# test.net
KiCad netlist of a schematic drawn in EAGLE
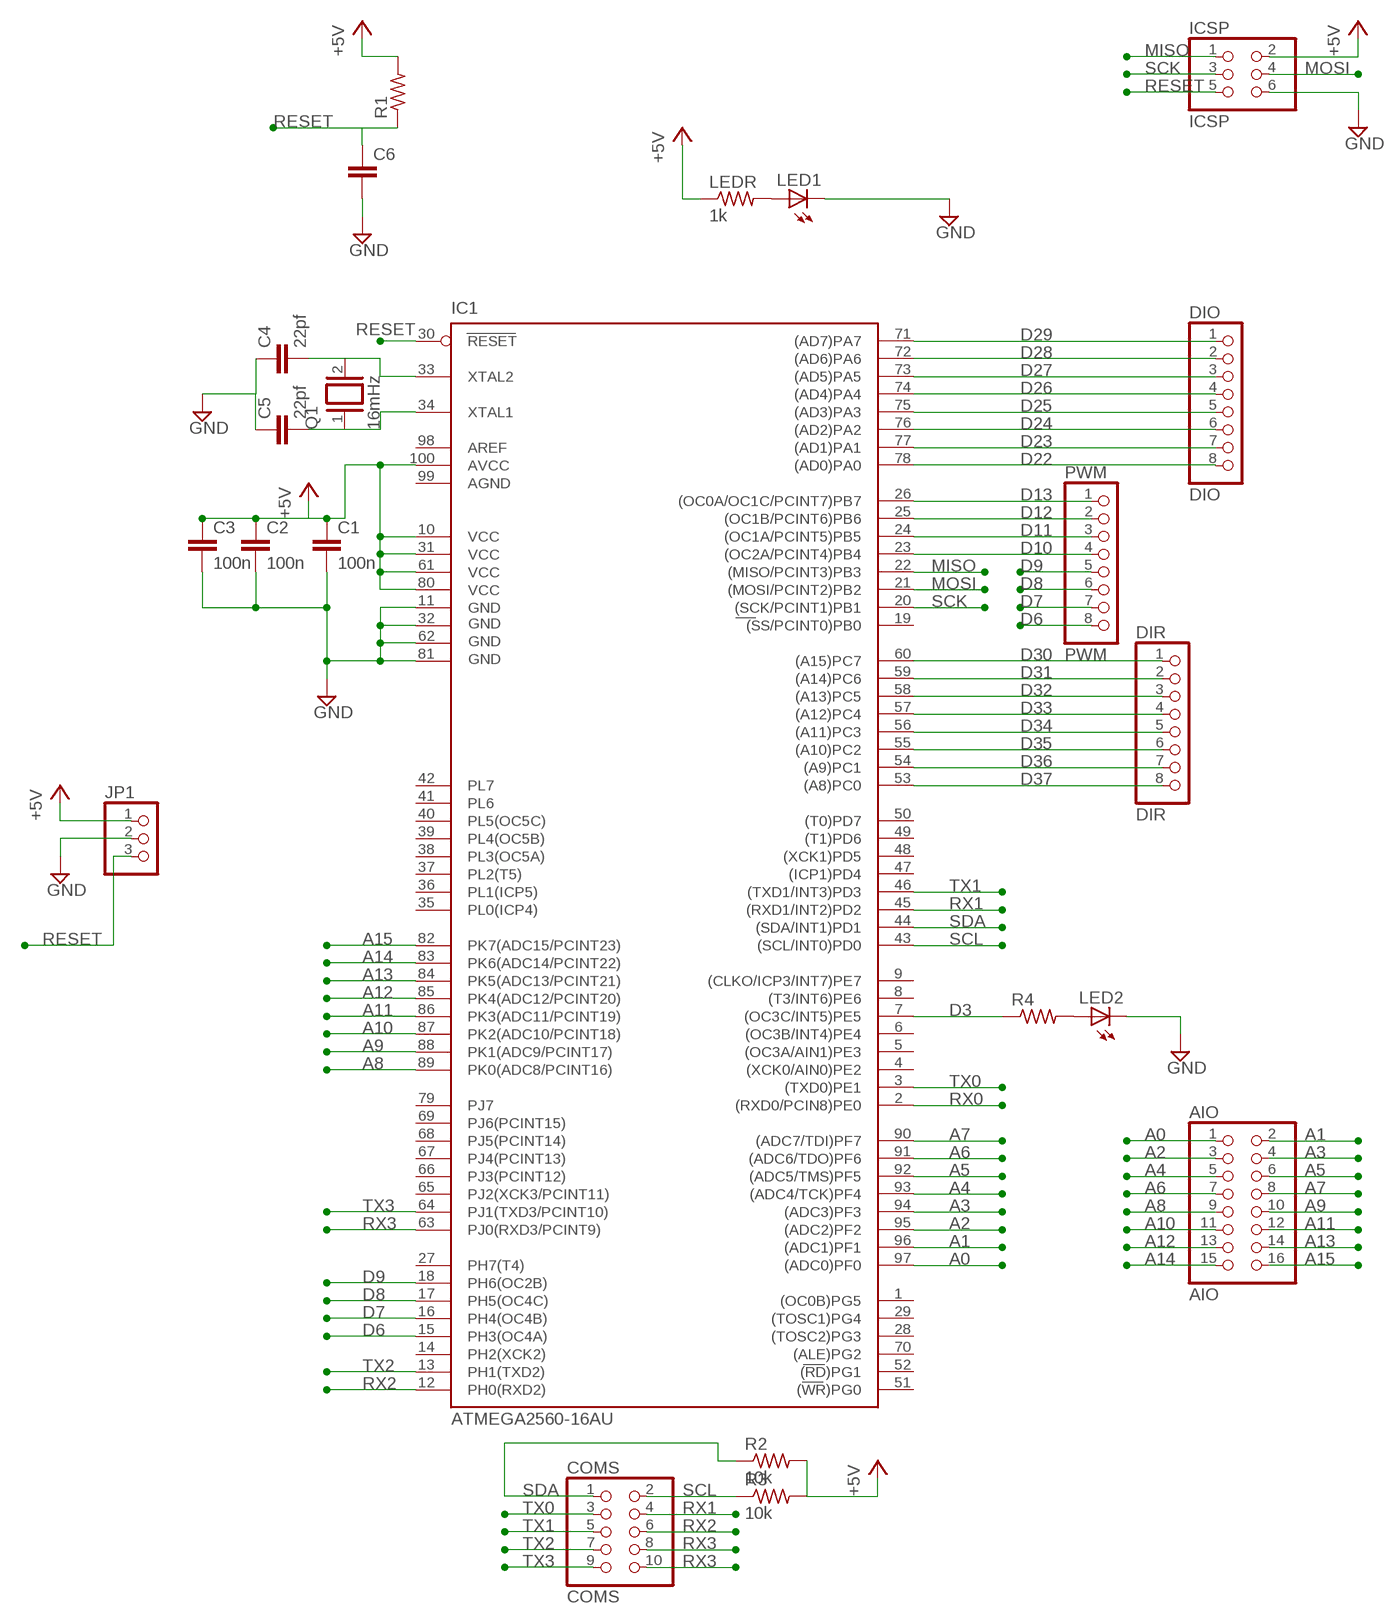
[diagram p0: schematic, sheet 1]

(export (version "E")
  (design (tool "Eeschema 10.0.6"))
  (components
    (comp (ref "AIO")
      (value "AIO")
      (footprint "eagle-import:2X08")
      (libsource (lib "eagle-import") (part "PINHD-2X8"))
    )
    (comp (ref "C1")
      (value "100n")
      (footprint "eagle-import:C5B3.5")
      (libsource (lib "eagle-import") (part "C5/3.5"))
    )
    (comp (ref "C2")
      (value "100n")
      (footprint "eagle-import:C5B3.5")
      (libsource (lib "eagle-import") (part "C5/3.5"))
    )
    (comp (ref "C3")
      (value "100n")
      (footprint "eagle-import:C5B3.5")
      (libsource (lib "eagle-import") (part "C5/3.5"))
    )
    (comp (ref "C4")
      (value "22pf")
      (footprint "eagle-import:C5B3.5")
      (libsource (lib "eagle-import") (part "C5/3.5"))
    )
    (comp (ref "C5")
      (value "22pf")
      (footprint "eagle-import:C5B3.5")
      (libsource (lib "eagle-import") (part "C5/3.5"))
    )
    (comp (ref "C6")
      (value "C5/3.5")
      (footprint "eagle-import:C5B3.5")
      (libsource (lib "eagle-import") (part "C5/3.5"))
    )
    (comp (ref "COMS")
      (value "COMS")
      (footprint "eagle-import:2X05")
      (libsource (lib "eagle-import") (part "PINHD-2X5"))
    )
    (comp (ref "DIO")
      (value "DIO")
      (footprint "eagle-import:1X08")
      (libsource (lib "eagle-import") (part "PINHD-1X8"))
    )
    (comp (ref "DIR")
      (value "DIR")
      (footprint "eagle-import:1X08")
      (libsource (lib "eagle-import") (part "PINHD-1X8"))
    )
    (comp (ref "IC1")
      (value "ATMEGA2560-16AU")
      (footprint "eagle-import:TQFP100")
      (libsource (lib "eagle-import") (part "ATMEGAAU2560-16"))
    )
    (comp (ref "ICSP")
      (value "ICSP")
      (footprint "eagle-import:2X03")
      (libsource (lib "eagle-import") (part "PINHD-2X3"))
    )
    (comp (ref "JP1")
      (value "PINHD-1X3")
      (footprint "eagle-import:1X03")
      (libsource (lib "eagle-import") (part "PINHD-1X3"))
    )
    (comp (ref "LED1")
      (value "LEDB156")
      (footprint "eagle-import:Q62902-B156")
      (libsource (lib "eagle-import") (part "LEDB156"))
    )
    (comp (ref "LED2")
      (value "LEDB156")
      (footprint "eagle-import:Q62902-B156")
      (libsource (lib "eagle-import") (part "LEDB156"))
    )
    (comp (ref "LEDR")
      (value "1k")
      (footprint "eagle-import:0207_7")
      (libsource (lib "eagle-import") (part "R-US_0207/7"))
    )
    (comp (ref "PWM")
      (value "PWM")
      (footprint "eagle-import:1X08")
      (libsource (lib "eagle-import") (part "PINHD-1X8"))
    )
    (comp (ref "Q1")
      (value "16mHz")
      (footprint "eagle-import:QS")
      (libsource (lib "eagle-import") (part "XTAL/S"))
    )
    (comp (ref "R1")
      (value "R-US_0207/7")
      (footprint "eagle-import:0207_7")
      (libsource (lib "eagle-import") (part "R-US_0207/7"))
    )
    (comp (ref "R2")
      (value "10k")
      (footprint "eagle-import:0207_7")
      (libsource (lib "eagle-import") (part "resistor_R-US_0207/7"))
    )
    (comp (ref "R3")
      (value "10k")
      (footprint "eagle-import:0207_7")
      (libsource (lib "eagle-import") (part "resistor_R-US_0207/7"))
    )
    (comp (ref "R4")
      (value "R-US_0207/7")
      (footprint "eagle-import:0207_7")
      (libsource (lib "eagle-import") (part "resistor_R-US_0207/7"))
    )
  )
  (nets
    (net (code "1") (name "+5V") (class "Default")
      (node (ref "C1") (pin "1") (pinfunction "1_1") (pintype "passive"))
      (node (ref "C2") (pin "1") (pinfunction "1_1") (pintype "passive"))
      (node (ref "C3") (pin "1") (pinfunction "1_1") (pintype "passive"))
      (node (ref "IC1") (pin "10") (pinfunction "VCC_10") (pintype "power_in"))
      (node (ref "IC1") (pin "100") (pinfunction "AVCC_100") (pintype "power_in"))
      (node (ref "IC1") (pin "31") (pinfunction "VCC1_31") (pintype "power_in"))
      (node (ref "IC1") (pin "61") (pinfunction "VCC2_61") (pintype "power_in"))
      (node (ref "IC1") (pin "80") (pinfunction "VCC3_80") (pintype "power_in"))
      (node (ref "ICSP") (pin "2") (pinfunction "2_2") (pintype "passive"))
      (node (ref "JP1") (pin "1") (pinfunction "1_1") (pintype "passive"))
      (node (ref "LEDR") (pin "1") (pinfunction "1_1") (pintype "passive"))
      (node (ref "R1") (pin "2") (pinfunction "2_2") (pintype "passive"))
      (node (ref "R2") (pin "2") (pinfunction "2_2") (pintype "passive"))
      (node (ref "R3") (pin "2") (pinfunction "2_2") (pintype "passive"))
    )
    (net (code "2") (name "/A0") (class "Default")
      (node (ref "AIO") (pin "1") (pinfunction "1_1") (pintype "passive"))
      (node (ref "IC1") (pin "97") (pinfunction "(ADC0)PF0_97") (pintype "bidirectional"))
    )
    (net (code "3") (name "/A1") (class "Default")
      (node (ref "AIO") (pin "2") (pinfunction "2_2") (pintype "passive"))
      (node (ref "IC1") (pin "96") (pinfunction "(ADC1)PF1_96") (pintype "bidirectional"))
    )
    (net (code "4") (name "/A2") (class "Default")
      (node (ref "AIO") (pin "3") (pinfunction "3_3") (pintype "passive"))
      (node (ref "IC1") (pin "95") (pinfunction "(ADC2)PF2_95") (pintype "bidirectional"))
    )
    (net (code "5") (name "/A3") (class "Default")
      (node (ref "AIO") (pin "4") (pinfunction "4_4") (pintype "passive"))
      (node (ref "IC1") (pin "94") (pinfunction "(ADC3)PF3_94") (pintype "bidirectional"))
    )
    (net (code "6") (name "/A4") (class "Default")
      (node (ref "AIO") (pin "5") (pinfunction "5_5") (pintype "passive"))
      (node (ref "IC1") (pin "93") (pinfunction "(ADC4/TCK)PF4_93") (pintype "bidirectional"))
    )
    (net (code "7") (name "/A5") (class "Default")
      (node (ref "AIO") (pin "6") (pinfunction "6_6") (pintype "passive"))
      (node (ref "IC1") (pin "92") (pinfunction "(ADC5/TMS)PF5_92") (pintype "bidirectional"))
    )
    (net (code "8") (name "/A6") (class "Default")
      (node (ref "AIO") (pin "7") (pinfunction "7_7") (pintype "passive"))
      (node (ref "IC1") (pin "91") (pinfunction "(ADC6/TDO)PF6_91") (pintype "bidirectional"))
    )
    (net (code "9") (name "/A7") (class "Default")
      (node (ref "AIO") (pin "8") (pinfunction "8_8") (pintype "passive"))
      (node (ref "IC1") (pin "90") (pinfunction "(ADC7/TDI)PF7_90") (pintype "bidirectional"))
    )
    (net (code "10") (name "/A8") (class "Default")
      (node (ref "AIO") (pin "9") (pinfunction "9_9") (pintype "passive"))
      (node (ref "IC1") (pin "89") (pinfunction "PK0(ADC8/PCINT16)_89") (pintype "bidirectional"))
    )
    (net (code "11") (name "/A9") (class "Default")
      (node (ref "AIO") (pin "10") (pinfunction "10_10") (pintype "passive"))
      (node (ref "IC1") (pin "88") (pinfunction "PK1(ADC9/PCINT17)_88") (pintype "bidirectional"))
    )
    (net (code "12") (name "/A10") (class "Default")
      (node (ref "AIO") (pin "11") (pinfunction "11_11") (pintype "passive"))
      (node (ref "IC1") (pin "87") (pinfunction "PK2(ADC10/PCINT18)_87") (pintype "bidirectional"))
    )
    (net (code "13") (name "/A11") (class "Default")
      (node (ref "AIO") (pin "12") (pinfunction "12_12") (pintype "passive"))
      (node (ref "IC1") (pin "86") (pinfunction "PK3(ADC11/PCINT19)_86") (pintype "bidirectional"))
    )
    (net (code "14") (name "/A12") (class "Default")
      (node (ref "AIO") (pin "13") (pinfunction "13_13") (pintype "passive"))
      (node (ref "IC1") (pin "85") (pinfunction "PK4(ADC12/PCINT20)_85") (pintype "bidirectional"))
    )
    (net (code "15") (name "/A13") (class "Default")
      (node (ref "AIO") (pin "14") (pinfunction "14_14") (pintype "passive"))
      (node (ref "IC1") (pin "84") (pinfunction "PK5(ADC13/PCINT21)_84") (pintype "bidirectional"))
    )
    (net (code "16") (name "/A14") (class "Default")
      (node (ref "AIO") (pin "15") (pinfunction "15_15") (pintype "passive"))
      (node (ref "IC1") (pin "83") (pinfunction "PK6(ADC14/PCINT22)_83") (pintype "bidirectional"))
    )
    (net (code "17") (name "/A15") (class "Default")
      (node (ref "AIO") (pin "16") (pinfunction "16_16") (pintype "passive"))
      (node (ref "IC1") (pin "82") (pinfunction "PK7(ADC15/PCINT23)_82") (pintype "bidirectional"))
    )
    (net (code "18") (name "/AGND") (class "Default")
      (node (ref "IC1") (pin "99") (pinfunction "AGND_99") (pintype "power_in"))
    )
    (net (code "19") (name "/D3") (class "Default")
      (node (ref "IC1") (pin "7") (pinfunction "(OC3C/INT5)PE5_7") (pintype "bidirectional"))
      (node (ref "R4") (pin "1") (pinfunction "1_1") (pintype "passive"))
    )
    (net (code "20") (name "/D6") (class "Default")
      (node (ref "IC1") (pin "15") (pinfunction "PH3(OC4A)_15") (pintype "bidirectional"))
      (node (ref "PWM") (pin "8") (pinfunction "8_8") (pintype "passive"))
    )
    (net (code "21") (name "/D7") (class "Default")
      (node (ref "IC1") (pin "16") (pinfunction "PH4(OC4B)_16") (pintype "bidirectional"))
      (node (ref "PWM") (pin "7") (pinfunction "7_7") (pintype "passive"))
    )
    (net (code "22") (name "/D8") (class "Default")
      (node (ref "IC1") (pin "17") (pinfunction "PH5(OC4C)_17") (pintype "bidirectional"))
      (node (ref "PWM") (pin "6") (pinfunction "6_6") (pintype "passive"))
    )
    (net (code "23") (name "/D9") (class "Default")
      (node (ref "IC1") (pin "18") (pinfunction "PH6(OC2B)_18") (pintype "bidirectional"))
      (node (ref "PWM") (pin "5") (pinfunction "5_5") (pintype "passive"))
    )
    (net (code "24") (name "/D10") (class "Default")
      (node (ref "IC1") (pin "23") (pinfunction "(OC2A/PCINT4)PB4_23") (pintype "bidirectional"))
      (node (ref "PWM") (pin "4") (pinfunction "4_4") (pintype "passive"))
    )
    (net (code "25") (name "/D11") (class "Default")
      (node (ref "IC1") (pin "24") (pinfunction "(OC1A/PCINT5)PB5_24") (pintype "bidirectional"))
      (node (ref "PWM") (pin "3") (pinfunction "3_3") (pintype "passive"))
    )
    (net (code "26") (name "/D12") (class "Default")
      (node (ref "IC1") (pin "25") (pinfunction "(OC1B/PCINT6)PB6_25") (pintype "bidirectional"))
      (node (ref "PWM") (pin "2") (pinfunction "2_2") (pintype "passive"))
    )
    (net (code "27") (name "/D13") (class "Default")
      (node (ref "IC1") (pin "26") (pinfunction "(OC0A/OC1C/PCINT7)PB7_26") (pintype "bidirectional"))
      (node (ref "PWM") (pin "1") (pinfunction "1_1") (pintype "passive"))
    )
    (net (code "28") (name "/D22") (class "Default")
      (node (ref "DIO") (pin "8") (pinfunction "8_8") (pintype "passive"))
      (node (ref "IC1") (pin "78") (pinfunction "(AD0)PA0_78") (pintype "bidirectional"))
    )
    (net (code "29") (name "/D23") (class "Default")
      (node (ref "DIO") (pin "7") (pinfunction "7_7") (pintype "passive"))
      (node (ref "IC1") (pin "77") (pinfunction "(AD1)PA1_77") (pintype "bidirectional"))
    )
    (net (code "30") (name "/D24") (class "Default")
      (node (ref "DIO") (pin "6") (pinfunction "6_6") (pintype "passive"))
      (node (ref "IC1") (pin "76") (pinfunction "(AD2)PA2_76") (pintype "bidirectional"))
    )
    (net (code "31") (name "/D25") (class "Default")
      (node (ref "DIO") (pin "5") (pinfunction "5_5") (pintype "passive"))
      (node (ref "IC1") (pin "75") (pinfunction "(AD3)PA3_75") (pintype "bidirectional"))
    )
    (net (code "32") (name "/D26") (class "Default")
      (node (ref "DIO") (pin "4") (pinfunction "4_4") (pintype "passive"))
      (node (ref "IC1") (pin "74") (pinfunction "(AD4)PA4_74") (pintype "bidirectional"))
    )
    (net (code "33") (name "/D27") (class "Default")
      (node (ref "DIO") (pin "3") (pinfunction "3_3") (pintype "passive"))
      (node (ref "IC1") (pin "73") (pinfunction "(AD5)PA5_73") (pintype "bidirectional"))
    )
    (net (code "34") (name "/D28") (class "Default")
      (node (ref "DIO") (pin "2") (pinfunction "2_2") (pintype "passive"))
      (node (ref "IC1") (pin "72") (pinfunction "(AD6)PA6_72") (pintype "bidirectional"))
    )
    (net (code "35") (name "/D29") (class "Default")
      (node (ref "DIO") (pin "1") (pinfunction "1_1") (pintype "passive"))
      (node (ref "IC1") (pin "71") (pinfunction "(AD7)PA7_71") (pintype "bidirectional"))
    )
    (net (code "36") (name "/D30") (class "Default")
      (node (ref "DIR") (pin "1") (pinfunction "1_1") (pintype "passive"))
      (node (ref "IC1") (pin "60") (pinfunction "(A15)PC7_60") (pintype "bidirectional"))
    )
    (net (code "37") (name "/D31") (class "Default")
      (node (ref "DIR") (pin "2") (pinfunction "2_2") (pintype "passive"))
      (node (ref "IC1") (pin "59") (pinfunction "(A14)PC6_59") (pintype "bidirectional"))
    )
    (net (code "38") (name "/D32") (class "Default")
      (node (ref "DIR") (pin "3") (pinfunction "3_3") (pintype "passive"))
      (node (ref "IC1") (pin "58") (pinfunction "(A13)PC5_58") (pintype "bidirectional"))
    )
    (net (code "39") (name "/D33") (class "Default")
      (node (ref "DIR") (pin "4") (pinfunction "4_4") (pintype "passive"))
      (node (ref "IC1") (pin "57") (pinfunction "(A12)PC4_57") (pintype "bidirectional"))
    )
    (net (code "40") (name "/D34") (class "Default")
      (node (ref "DIR") (pin "5") (pinfunction "5_5") (pintype "passive"))
      (node (ref "IC1") (pin "56") (pinfunction "(A11)PC3_56") (pintype "bidirectional"))
    )
    (net (code "41") (name "/D35") (class "Default")
      (node (ref "DIR") (pin "6") (pinfunction "6_6") (pintype "passive"))
      (node (ref "IC1") (pin "55") (pinfunction "(A10)PC2_55") (pintype "bidirectional"))
    )
    (net (code "42") (name "/D36") (class "Default")
      (node (ref "DIR") (pin "7") (pinfunction "7_7") (pintype "passive"))
      (node (ref "IC1") (pin "54") (pinfunction "(A9)PC1_54") (pintype "bidirectional"))
    )
    (net (code "43") (name "/D37") (class "Default")
      (node (ref "DIR") (pin "8") (pinfunction "8_8") (pintype "passive"))
      (node (ref "IC1") (pin "53") (pinfunction "(A8)PC0_53") (pintype "bidirectional"))
    )
    (net (code "44") (name "/MISO") (class "Default")
      (node (ref "IC1") (pin "22") (pinfunction "(MISO/PCINT3)PB3_22") (pintype "bidirectional"))
      (node (ref "ICSP") (pin "1") (pinfunction "1_1") (pintype "passive"))
    )
    (net (code "45") (name "/MOSI") (class "Default")
      (node (ref "IC1") (pin "21") (pinfunction "(MOSI/PCINT2)PB2_21") (pintype "bidirectional"))
      (node (ref "ICSP") (pin "4") (pinfunction "4_4") (pintype "passive"))
    )
    (net (code "46") (name "/RESET") (class "Default")
      (node (ref "C6") (pin "1") (pinfunction "1_1") (pintype "passive"))
      (node (ref "IC1") (pin "30") (pinfunction "RESET_30") (pintype "input"))
      (node (ref "ICSP") (pin "5") (pinfunction "5_5") (pintype "passive"))
      (node (ref "JP1") (pin "3") (pinfunction "3_3") (pintype "passive"))
      (node (ref "R1") (pin "1") (pinfunction "1_1") (pintype "passive"))
    )
    (net (code "47") (name "/RX0") (class "Default")
      (node (ref "IC1") (pin "2") (pinfunction "(RXD0/PCIN8)PE0_2") (pintype "bidirectional"))
    )
    (net (code "48") (name "/RX1") (class "Default")
      (node (ref "COMS") (pin "4") (pinfunction "4_4") (pintype "passive"))
      (node (ref "IC1") (pin "45") (pinfunction "(RXD1/INT2)PD2_45") (pintype "bidirectional"))
    )
    (net (code "49") (name "/RX2") (class "Default")
      (node (ref "COMS") (pin "6") (pinfunction "6_6") (pintype "passive"))
      (node (ref "IC1") (pin "12") (pinfunction "PH0(RXD2)_12") (pintype "bidirectional"))
    )
    (net (code "50") (name "/RX3") (class "Default")
      (node (ref "COMS") (pin "10") (pinfunction "10_10") (pintype "passive"))
      (node (ref "COMS") (pin "8") (pinfunction "8_8") (pintype "passive"))
      (node (ref "IC1") (pin "63") (pinfunction "PJ0(RXD3/PCINT9)_63") (pintype "bidirectional"))
    )
    (net (code "51") (name "/SCK") (class "Default")
      (node (ref "IC1") (pin "20") (pinfunction "(SCK/PCINT1)PB1_20") (pintype "bidirectional"))
      (node (ref "ICSP") (pin "3") (pinfunction "3_3") (pintype "passive"))
    )
    (net (code "52") (name "/SCL") (class "Default")
      (node (ref "COMS") (pin "2") (pinfunction "2_2") (pintype "passive"))
      (node (ref "IC1") (pin "43") (pinfunction "(SCL/INT0)PD0_43") (pintype "bidirectional"))
      (node (ref "R3") (pin "1") (pinfunction "1_1") (pintype "passive"))
    )
    (net (code "53") (name "/SDA") (class "Default")
      (node (ref "COMS") (pin "1") (pinfunction "1_1") (pintype "passive"))
      (node (ref "IC1") (pin "44") (pinfunction "(SDA/INT1)PD1_44") (pintype "bidirectional"))
      (node (ref "R2") (pin "1") (pinfunction "1_1") (pintype "passive"))
    )
    (net (code "54") (name "/TX0") (class "Default")
      (node (ref "COMS") (pin "3") (pinfunction "3_3") (pintype "passive"))
      (node (ref "IC1") (pin "3") (pinfunction "(TXD0)PE1_3") (pintype "bidirectional"))
    )
    (net (code "55") (name "/TX1") (class "Default")
      (node (ref "COMS") (pin "5") (pinfunction "5_5") (pintype "passive"))
      (node (ref "IC1") (pin "46") (pinfunction "(TXD1/INT3)PD3_46") (pintype "bidirectional"))
    )
    (net (code "56") (name "/TX2") (class "Default")
      (node (ref "COMS") (pin "7") (pinfunction "7_7") (pintype "passive"))
      (node (ref "IC1") (pin "13") (pinfunction "PH1(TXD2)_13") (pintype "bidirectional"))
    )
    (net (code "57") (name "/TX3") (class "Default")
      (node (ref "COMS") (pin "9") (pinfunction "9_9") (pintype "passive"))
      (node (ref "IC1") (pin "64") (pinfunction "PJ1(TXD3/PCINT10)_64") (pintype "bidirectional"))
    )
    (net (code "58") (name "GND") (class "Default")
      (node (ref "C1") (pin "2") (pinfunction "2_2") (pintype "passive"))
      (node (ref "C2") (pin "2") (pinfunction "2_2") (pintype "passive"))
      (node (ref "C3") (pin "2") (pinfunction "2_2") (pintype "passive"))
      (node (ref "C4") (pin "1") (pinfunction "1_1") (pintype "passive"))
      (node (ref "C5") (pin "1") (pinfunction "1_1") (pintype "passive"))
      (node (ref "C6") (pin "2") (pinfunction "2_2") (pintype "passive"))
      (node (ref "IC1") (pin "11") (pinfunction "GND_11") (pintype "power_in"))
      (node (ref "IC1") (pin "32") (pinfunction "GND1_32") (pintype "power_in"))
      (node (ref "IC1") (pin "62") (pinfunction "GND2_62") (pintype "power_in"))
      (node (ref "IC1") (pin "81") (pinfunction "GND3_81") (pintype "power_in"))
      (node (ref "ICSP") (pin "6") (pinfunction "6_6") (pintype "passive"))
      (node (ref "JP1") (pin "2") (pinfunction "2_2") (pintype "passive"))
      (node (ref "LED1") (pin "K") (pinfunction "C_K") (pintype "passive"))
      (node (ref "LED2") (pin "K") (pinfunction "C_K") (pintype "passive"))
    )
    (net (code "59") (name "Net-(IC1-XTAL1)") (class "Default")
      (node (ref "C5") (pin "2") (pinfunction "2_2") (pintype "passive"))
      (node (ref "IC1") (pin "34") (pinfunction "XTAL1_34") (pintype "input"))
      (node (ref "Q1") (pin "1") (pinfunction "1_1") (pintype "passive"))
    )
    (net (code "60") (name "Net-(IC1-XTAL2)") (class "Default")
      (node (ref "C4") (pin "2") (pinfunction "2_2") (pintype "passive"))
      (node (ref "IC1") (pin "33") (pinfunction "XTAL2_33") (pintype "output"))
      (node (ref "Q1") (pin "2") (pinfunction "2_2") (pintype "passive"))
    )
    (net (code "61") (name "Net-(LED1-PadA)") (class "Default")
      (node (ref "LED1") (pin "A") (pinfunction "A_A") (pintype "passive"))
      (node (ref "LEDR") (pin "2") (pinfunction "2_2") (pintype "passive"))
    )
    (net (code "62") (name "Net-(LED2-PadA)") (class "Default")
      (node (ref "LED2") (pin "A") (pinfunction "A_A") (pintype "passive"))
      (node (ref "R4") (pin "2") (pinfunction "2_2") (pintype "passive"))
    )
    (net (code "63") (name "unconnected-(IC1-(ALE)PG2-Pad70)") (class "Default")
      (node (ref "IC1") (pin "70") (pinfunction "(ALE)PG2_70") (pintype "bidirectional"))
    )
    (net (code "64") (name "unconnected-(IC1-(CLKO{slash}ICP3{slash}INT7)PE7-Pad9)") (class "Default")
      (node (ref "IC1") (pin "9") (pinfunction "(CLKO/ICP3/INT7)PE7_9") (pintype "bidirectional"))
    )
    (net (code "65") (name "unconnected-(IC1-(ICP1)PD4-Pad47)") (class "Default")
      (node (ref "IC1") (pin "47") (pinfunction "(ICP1)PD4_47") (pintype "bidirectional"))
    )
    (net (code "66") (name "unconnected-(IC1-(OC0B)PG5-Pad1)") (class "Default")
      (node (ref "IC1") (pin "1") (pinfunction "(OC0B)PG5_1") (pintype "bidirectional"))
    )
    (net (code "67") (name "unconnected-(IC1-(OC3A{slash}AIN1)PE3-Pad5)") (class "Default")
      (node (ref "IC1") (pin "5") (pinfunction "(OC3A/AIN1)PE3_5") (pintype "bidirectional"))
    )
    (net (code "68") (name "unconnected-(IC1-(OC3B{slash}INT4)PE4-Pad6)") (class "Default")
      (node (ref "IC1") (pin "6") (pinfunction "(OC3B/INT4)PE4_6") (pintype "bidirectional"))
    )
    (net (code "69") (name "unconnected-(IC1-(RD)PG1-Pad52)") (class "Default")
      (node (ref "IC1") (pin "52") (pinfunction "(RD)PG1_52") (pintype "bidirectional"))
    )
    (net (code "70") (name "unconnected-(IC1-(SS{slash}PCINT0)PB0-Pad19)") (class "Default")
      (node (ref "IC1") (pin "19") (pinfunction "(SS/PCINT0)PB0_19") (pintype "bidirectional"))
    )
    (net (code "71") (name "unconnected-(IC1-(T0)PD7-Pad50)") (class "Default")
      (node (ref "IC1") (pin "50") (pinfunction "(T0)PD7_50") (pintype "bidirectional"))
    )
    (net (code "72") (name "unconnected-(IC1-(T1)PD6-Pad49)") (class "Default")
      (node (ref "IC1") (pin "49") (pinfunction "(T1)PD6_49") (pintype "bidirectional"))
    )
    (net (code "73") (name "unconnected-(IC1-(T3{slash}INT6)PE6-Pad8)") (class "Default")
      (node (ref "IC1") (pin "8") (pinfunction "(T3/INT6)PE6_8") (pintype "bidirectional"))
    )
    (net (code "74") (name "unconnected-(IC1-(TOSC1)PG4-Pad29)") (class "Default")
      (node (ref "IC1") (pin "29") (pinfunction "(TOSC1)PG4_29") (pintype "bidirectional"))
    )
    (net (code "75") (name "unconnected-(IC1-(TOSC2)PG3-Pad28)") (class "Default")
      (node (ref "IC1") (pin "28") (pinfunction "(TOSC2)PG3_28") (pintype "bidirectional"))
    )
    (net (code "76") (name "unconnected-(IC1-(WR)PG0-Pad51)") (class "Default")
      (node (ref "IC1") (pin "51") (pinfunction "(WR)PG0_51") (pintype "bidirectional"))
    )
    (net (code "77") (name "unconnected-(IC1-(XCK0{slash}AIN0)PE2-Pad4)") (class "Default")
      (node (ref "IC1") (pin "4") (pinfunction "(XCK0/AIN0)PE2_4") (pintype "bidirectional"))
    )
    (net (code "78") (name "unconnected-(IC1-(XCK1)PD5-Pad48)") (class "Default")
      (node (ref "IC1") (pin "48") (pinfunction "(XCK1)PD5_48") (pintype "bidirectional"))
    )
    (net (code "79") (name "unconnected-(IC1-AREF-Pad98)") (class "Default")
      (node (ref "IC1") (pin "98") (pinfunction "AREF_98") (pintype "bidirectional"))
    )
    (net (code "80") (name "unconnected-(IC1-PH2(XCK2)-Pad14)") (class "Default")
      (node (ref "IC1") (pin "14") (pinfunction "PH2(XCK2)_14") (pintype "bidirectional"))
    )
    (net (code "81") (name "unconnected-(IC1-PH7(T4)-Pad27)") (class "Default")
      (node (ref "IC1") (pin "27") (pinfunction "PH7(T4)_27") (pintype "bidirectional"))
    )
    (net (code "82") (name "unconnected-(IC1-PJ2(XCK3{slash}PCINT11)-Pad65)") (class "Default")
      (node (ref "IC1") (pin "65") (pinfunction "PJ2(XCK3/PCINT11)_65") (pintype "bidirectional"))
    )
    (net (code "83") (name "unconnected-(IC1-PJ3(PCINT12)-Pad66)") (class "Default")
      (node (ref "IC1") (pin "66") (pinfunction "PJ3(PCINT12)_66") (pintype "bidirectional"))
    )
    (net (code "84") (name "unconnected-(IC1-PJ4(PCINT13)-Pad67)") (class "Default")
      (node (ref "IC1") (pin "67") (pinfunction "PJ4(PCINT13)_67") (pintype "bidirectional"))
    )
    (net (code "85") (name "unconnected-(IC1-PJ5(PCINT14)-Pad68)") (class "Default")
      (node (ref "IC1") (pin "68") (pinfunction "PJ5(PCINT14)_68") (pintype "bidirectional"))
    )
    (net (code "86") (name "unconnected-(IC1-PJ6(PCINT15)-Pad69)") (class "Default")
      (node (ref "IC1") (pin "69") (pinfunction "PJ6(PCINT15)_69") (pintype "bidirectional"))
    )
    (net (code "87") (name "unconnected-(IC1-PJ7-Pad79)") (class "Default")
      (node (ref "IC1") (pin "79") (pinfunction "PJ7_79") (pintype "bidirectional"))
    )
    (net (code "88") (name "unconnected-(IC1-PL0(ICP4)-Pad35)") (class "Default")
      (node (ref "IC1") (pin "35") (pinfunction "PL0(ICP4)_35") (pintype "bidirectional"))
    )
    (net (code "89") (name "unconnected-(IC1-PL1(ICP5)-Pad36)") (class "Default")
      (node (ref "IC1") (pin "36") (pinfunction "PL1(ICP5)_36") (pintype "bidirectional"))
    )
    (net (code "90") (name "unconnected-(IC1-PL2(T5)-Pad37)") (class "Default")
      (node (ref "IC1") (pin "37") (pinfunction "PL2(T5)_37") (pintype "bidirectional"))
    )
    (net (code "91") (name "unconnected-(IC1-PL3(OC5A)-Pad38)") (class "Default")
      (node (ref "IC1") (pin "38") (pinfunction "PL3(OC5A)_38") (pintype "bidirectional"))
    )
    (net (code "92") (name "unconnected-(IC1-PL4(OC5B)-Pad39)") (class "Default")
      (node (ref "IC1") (pin "39") (pinfunction "PL4(OC5B)_39") (pintype "bidirectional"))
    )
    (net (code "93") (name "unconnected-(IC1-PL5(OC5C)-Pad40)") (class "Default")
      (node (ref "IC1") (pin "40") (pinfunction "PL5(OC5C)_40") (pintype "bidirectional"))
    )
    (net (code "94") (name "unconnected-(IC1-PL6-Pad41)") (class "Default")
      (node (ref "IC1") (pin "41") (pinfunction "PL6_41") (pintype "bidirectional"))
    )
    (net (code "95") (name "unconnected-(IC1-PL7-Pad42)") (class "Default")
      (node (ref "IC1") (pin "42") (pinfunction "PL7_42") (pintype "bidirectional"))
    )
  )
)
